# 2lampen.net
KiCad netlist of a schematic drawn in EAGLE
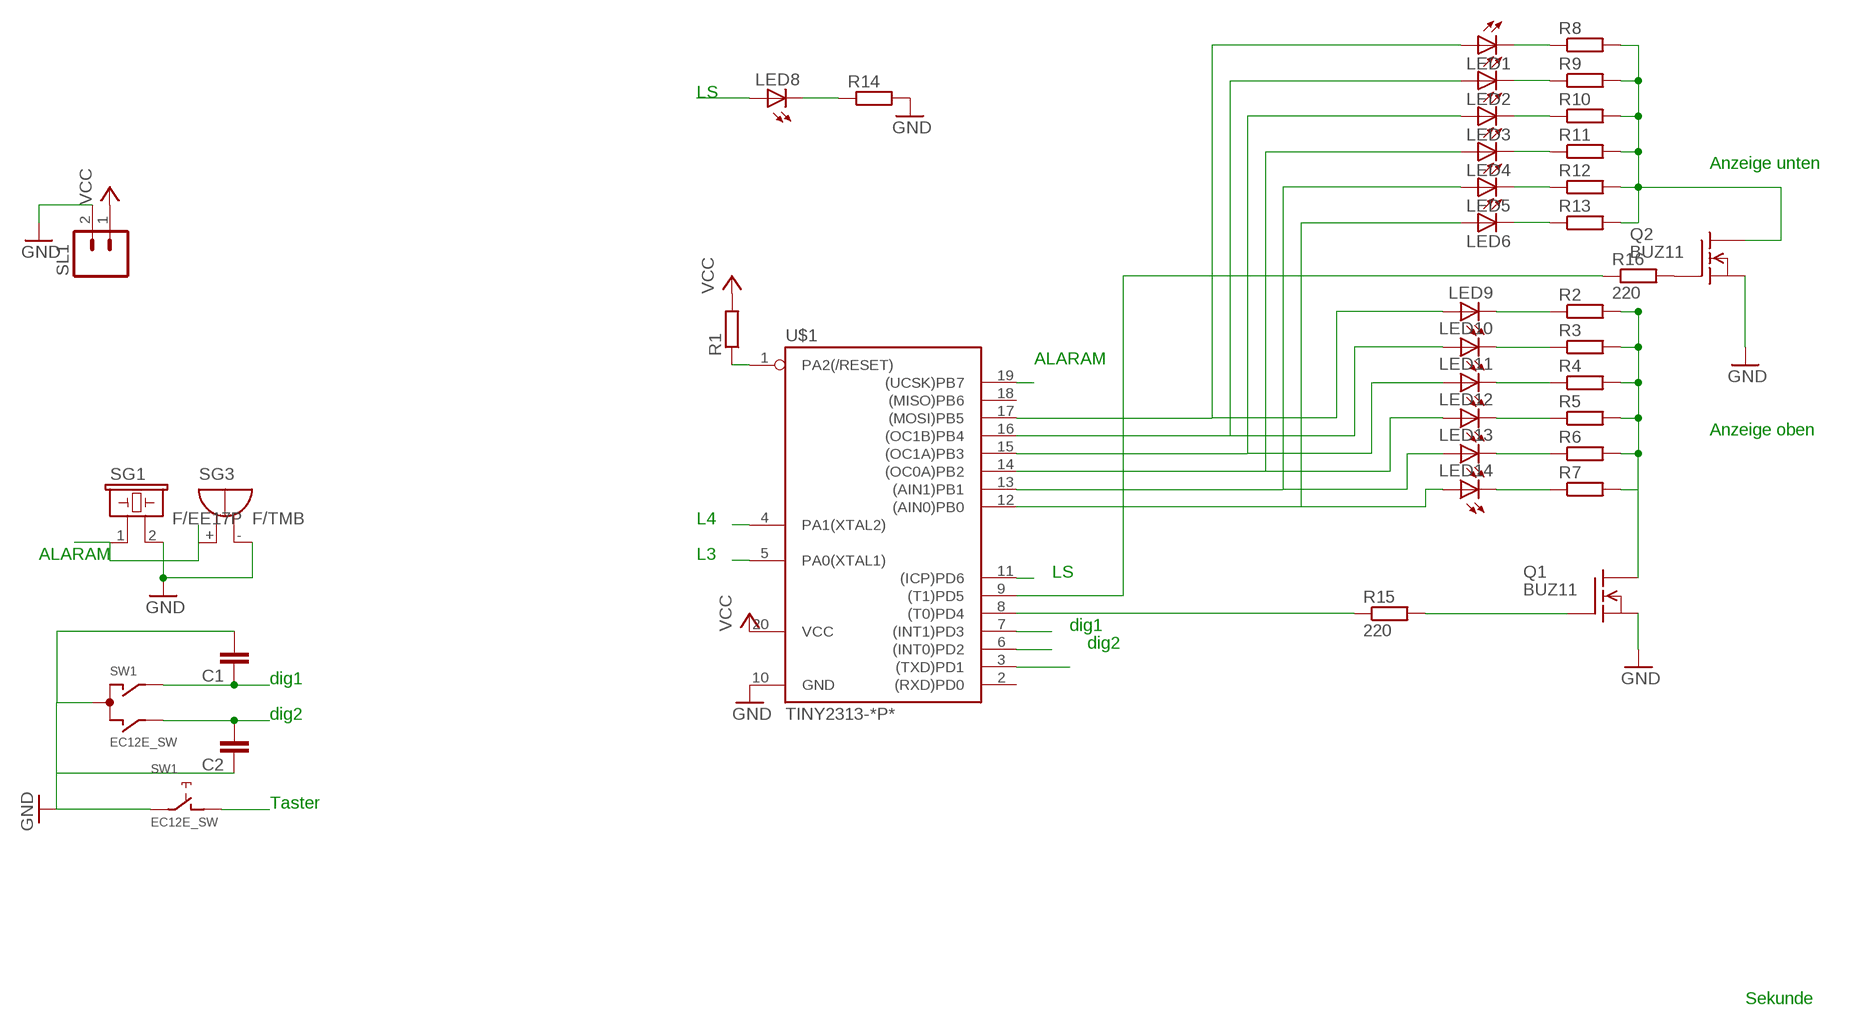
[diagram p0: schematic, sheet 1]

(export (version "E")
  (design (tool "Eeschema 10.0.6"))
  (components
    (comp (ref "C1")
      (value "C-EU025-025X050")
      (footprint "eagle-import:C025-025X050")
      (libsource (lib "eagle-import") (part "C-EU025-025X050"))
    )
    (comp (ref "C2")
      (value "C-EU025-025X050")
      (footprint "eagle-import:C025-025X050")
      (libsource (lib "eagle-import") (part "C-EU025-025X050"))
    )
    (comp (ref "LED1")
      (value "LED5MM")
      (footprint "eagle-import:LED5MM")
      (libsource (lib "eagle-import") (part "LED5MM"))
    )
    (comp (ref "LED2")
      (value "LED5MM")
      (footprint "eagle-import:LED5MM")
      (libsource (lib "eagle-import") (part "LED5MM"))
    )
    (comp (ref "LED3")
      (value "LED5MM")
      (footprint "eagle-import:LED5MM")
      (libsource (lib "eagle-import") (part "LED5MM"))
    )
    (comp (ref "LED4")
      (value "LED5MM")
      (footprint "eagle-import:LED5MM")
      (libsource (lib "eagle-import") (part "LED5MM"))
    )
    (comp (ref "LED5")
      (value "LED5MM")
      (footprint "eagle-import:LED5MM")
      (libsource (lib "eagle-import") (part "LED5MM"))
    )
    (comp (ref "LED6")
      (value "LED5MM")
      (footprint "eagle-import:LED5MM")
      (libsource (lib "eagle-import") (part "LED5MM"))
    )
    (comp (ref "LED8")
      (value "LED3MM")
      (footprint "eagle-import:LED3MM")
      (libsource (lib "eagle-import") (part "LED3MM"))
    )
    (comp (ref "LED9")
      (value "LED5MM")
      (footprint "eagle-import:LED5MM")
      (libsource (lib "eagle-import") (part "LED5MM"))
    )
    (comp (ref "LED10")
      (value "LED5MM")
      (footprint "eagle-import:LED5MM")
      (libsource (lib "eagle-import") (part "LED5MM"))
    )
    (comp (ref "LED11")
      (value "LED5MM")
      (footprint "eagle-import:LED5MM")
      (libsource (lib "eagle-import") (part "LED5MM"))
    )
    (comp (ref "LED12")
      (value "LED5MM")
      (footprint "eagle-import:LED5MM")
      (libsource (lib "eagle-import") (part "LED5MM"))
    )
    (comp (ref "LED13")
      (value "LED5MM")
      (footprint "eagle-import:LED5MM")
      (libsource (lib "eagle-import") (part "LED5MM"))
    )
    (comp (ref "LED14")
      (value "LED5MM")
      (footprint "eagle-import:LED5MM")
      (libsource (lib "eagle-import") (part "LED5MM"))
    )
    (comp (ref "Q1")
      (value "BUZ11")
      (footprint "eagle-import:TO220")
      (libsource (lib "eagle-import") (part "BUZ11"))
    )
    (comp (ref "Q2")
      (value "BUZ11")
      (footprint "eagle-import:TO220")
      (libsource (lib "eagle-import") (part "BUZ11"))
    )
    (comp (ref "R1")
      (value "R-EU_0204/7")
      (footprint "eagle-import:0204_7")
      (libsource (lib "eagle-import") (part "R-EU_0204/7"))
    )
    (comp (ref "R2")
      (value "R-EU_0204/2V")
      (footprint "eagle-import:0204V")
      (libsource (lib "eagle-import") (part "R-EU_0204/2V"))
    )
    (comp (ref "R3")
      (value "R-EU_0204/2V")
      (footprint "eagle-import:0204V")
      (libsource (lib "eagle-import") (part "R-EU_0204/2V"))
    )
    (comp (ref "R4")
      (value "R-EU_0204/2V")
      (footprint "eagle-import:0204V")
      (libsource (lib "eagle-import") (part "R-EU_0204/2V"))
    )
    (comp (ref "R5")
      (value "R-EU_0204/2V")
      (footprint "eagle-import:0204V")
      (libsource (lib "eagle-import") (part "R-EU_0204/2V"))
    )
    (comp (ref "R6")
      (value "R-EU_0204/2V")
      (footprint "eagle-import:0204V")
      (libsource (lib "eagle-import") (part "R-EU_0204/2V"))
    )
    (comp (ref "R7")
      (value "R-EU_0204/2V")
      (footprint "eagle-import:0204V")
      (libsource (lib "eagle-import") (part "R-EU_0204/2V"))
    )
    (comp (ref "R8")
      (value "R-EU_0204/2V")
      (footprint "eagle-import:0204V")
      (libsource (lib "eagle-import") (part "R-EU_0204/2V"))
    )
    (comp (ref "R9")
      (value "R-EU_0204/2V")
      (footprint "eagle-import:0204V")
      (libsource (lib "eagle-import") (part "R-EU_0204/2V"))
    )
    (comp (ref "R10")
      (value "R-EU_0204/2V")
      (footprint "eagle-import:0204V")
      (libsource (lib "eagle-import") (part "R-EU_0204/2V"))
    )
    (comp (ref "R11")
      (value "R-EU_0204/2V")
      (footprint "eagle-import:0204V")
      (libsource (lib "eagle-import") (part "R-EU_0204/2V"))
    )
    (comp (ref "R12")
      (value "R-EU_0204/2V")
      (footprint "eagle-import:0204V")
      (libsource (lib "eagle-import") (part "R-EU_0204/2V"))
    )
    (comp (ref "R13")
      (value "R-EU_0204/7")
      (footprint "eagle-import:0204_7")
      (libsource (lib "eagle-import") (part "R-EU_0204/7"))
    )
    (comp (ref "R14")
      (value "R-EU_0204/2V")
      (footprint "eagle-import:0204V")
      (libsource (lib "eagle-import") (part "R-EU_0204/2V"))
    )
    (comp (ref "R15")
      (value "220")
      (footprint "eagle-import:0204V")
      (libsource (lib "eagle-import") (part "R-EU_0204/2V"))
    )
    (comp (ref "R16")
      (value "220")
      (footprint "eagle-import:0204V")
      (libsource (lib "eagle-import") (part "R-EU_0204/2V"))
    )
    (comp (ref "SG1")
      (value "F/EE17P")
      (footprint "eagle-import:F_EE17P")
      (libsource (lib "eagle-import") (part "F/EE17P"))
    )
    (comp (ref "SG3")
      (value "F/TMB")
      (footprint "eagle-import:F_TMB")
      (libsource (lib "eagle-import") (part "F/TMB"))
    )
    (comp (ref "SL1")
      (value "M02")
      (footprint "eagle-import:02P")
      (libsource (lib "eagle-import") (part "M02"))
    )
    (comp (ref "SW1")
      (value "EC12E_SW")
      (footprint "eagle-import:ALPS_EC12E_SW")
      (fields (field (name "MPN") "EC12E2424407"))
      (libsource (lib "eagle-import") (part "EC12E_SW"))
    )
    (comp (ref "U$1")
      (value "TINY2313-*P*")
      (footprint "eagle-import:DIL20")
      (libsource (lib "eagle-import") (part "TINY2313-P"))
    )
  )
  (nets
    (net (code "1") (name "/ALARM") (class "Default")
      (node (ref "SG1") (pin "1") (pinfunction "1_1") (pintype "passive"))
      (node (ref "SG3") (pin "+") (pinfunction "+_+") (pintype "passive"))
      (node (ref "U$1") (pin "19") (pinfunction "(UCSK)PB7_19") (pintype "bidirectional"))
    )
    (net (code "2") (name "/DIG1") (class "Default")
      (node (ref "C1") (pin "1") (pinfunction "1_1") (pintype "passive"))
      (node (ref "SW1") (pin "A") (pinfunction "A_A") (pintype "passive"))
      (node (ref "U$1") (pin "7") (pinfunction "(INT1)PD3_7") (pintype "bidirectional"))
    )
    (net (code "3") (name "/DIG2") (class "Default")
      (node (ref "C2") (pin "2") (pinfunction "2_2") (pintype "passive"))
      (node (ref "SW1") (pin "B") (pinfunction "B_B") (pintype "passive"))
      (node (ref "U$1") (pin "6") (pinfunction "(INT0)PD2_6") (pintype "bidirectional"))
    )
    (net (code "4") (name "/L3") (class "Default")
      (node (ref "LED11") (pin "A") (pinfunction "A_A") (pintype "passive"))
      (node (ref "LED3") (pin "A") (pinfunction "A_A") (pintype "passive"))
      (node (ref "U$1") (pin "15") (pinfunction "(OC1A)PB3_15") (pintype "bidirectional"))
      (node (ref "U$1") (pin "5") (pinfunction "PA0(XTAL1)_5") (pintype "bidirectional"))
    )
    (net (code "5") (name "/L4") (class "Default")
      (node (ref "LED12") (pin "A") (pinfunction "A_A") (pintype "passive"))
      (node (ref "LED4") (pin "A") (pinfunction "A_A") (pintype "passive"))
      (node (ref "U$1") (pin "14") (pinfunction "(OC0A)PB2_14") (pintype "bidirectional"))
      (node (ref "U$1") (pin "4") (pinfunction "PA1(XTAL2)_4") (pintype "bidirectional"))
    )
    (net (code "6") (name "/LS") (class "Default")
      (node (ref "LED8") (pin "A") (pinfunction "A_A") (pintype "passive"))
      (node (ref "U$1") (pin "11") (pinfunction "(ICP)PD6_11") (pintype "bidirectional"))
    )
    (net (code "7") (name "GND") (class "Default")
      (node (ref "C1") (pin "2") (pinfunction "2_2") (pintype "passive"))
      (node (ref "C2") (pin "1") (pinfunction "1_1") (pintype "passive"))
      (node (ref "Q1") (pin "3") (pinfunction "S_3") (pintype "passive"))
      (node (ref "Q2") (pin "3") (pinfunction "S_3") (pintype "passive"))
      (node (ref "R14") (pin "2") (pinfunction "2_2") (pintype "passive"))
      (node (ref "SG1") (pin "2") (pinfunction "2_2") (pintype "passive"))
      (node (ref "SG3") (pin "-") (pinfunction "-_-") (pintype "passive"))
      (node (ref "SL1") (pin "2") (pinfunction "2_2") (pintype "passive"))
      (node (ref "SW1") (pin "C") (pinfunction "C_C") (pintype "passive"))
      (node (ref "SW1") (pin "E") (pinfunction "2_E") (pintype "passive"))
      (node (ref "U$1") (pin "10") (pinfunction "GND_10") (pintype "power_in"))
    )
    (net (code "8") (name "Net-(LED1-C)") (class "Default")
      (node (ref "LED1") (pin "K") (pinfunction "C_K") (pintype "passive"))
      (node (ref "R8") (pin "1") (pinfunction "1_1") (pintype "passive"))
    )
    (net (code "9") (name "Net-(LED2-C)") (class "Default")
      (node (ref "LED2") (pin "K") (pinfunction "C_K") (pintype "passive"))
      (node (ref "R9") (pin "1") (pinfunction "1_1") (pintype "passive"))
    )
    (net (code "10") (name "Net-(LED3-C)") (class "Default")
      (node (ref "LED3") (pin "K") (pinfunction "C_K") (pintype "passive"))
      (node (ref "R10") (pin "1") (pinfunction "1_1") (pintype "passive"))
    )
    (net (code "11") (name "Net-(LED4-C)") (class "Default")
      (node (ref "LED4") (pin "K") (pinfunction "C_K") (pintype "passive"))
      (node (ref "R11") (pin "1") (pinfunction "1_1") (pintype "passive"))
    )
    (net (code "12") (name "Net-(LED5-C)") (class "Default")
      (node (ref "LED5") (pin "K") (pinfunction "C_K") (pintype "passive"))
      (node (ref "R12") (pin "1") (pinfunction "1_1") (pintype "passive"))
    )
    (net (code "13") (name "Net-(LED6-C)") (class "Default")
      (node (ref "LED6") (pin "K") (pinfunction "C_K") (pintype "passive"))
      (node (ref "R13") (pin "1") (pinfunction "1_1") (pintype "passive"))
    )
    (net (code "14") (name "Net-(LED8-C)") (class "Default")
      (node (ref "LED8") (pin "K") (pinfunction "C_K") (pintype "passive"))
      (node (ref "R14") (pin "1") (pinfunction "1_1") (pintype "passive"))
    )
    (net (code "15") (name "Net-(LED9-C)") (class "Default")
      (node (ref "LED9") (pin "K") (pinfunction "C_K") (pintype "passive"))
      (node (ref "R2") (pin "1") (pinfunction "1_1") (pintype "passive"))
    )
    (net (code "16") (name "Net-(LED10-C)") (class "Default")
      (node (ref "LED10") (pin "K") (pinfunction "C_K") (pintype "passive"))
      (node (ref "R3") (pin "1") (pinfunction "1_1") (pintype "passive"))
    )
    (net (code "17") (name "Net-(LED11-C)") (class "Default")
      (node (ref "LED11") (pin "K") (pinfunction "C_K") (pintype "passive"))
      (node (ref "R4") (pin "1") (pinfunction "1_1") (pintype "passive"))
    )
    (net (code "18") (name "Net-(LED12-C)") (class "Default")
      (node (ref "LED12") (pin "K") (pinfunction "C_K") (pintype "passive"))
      (node (ref "R5") (pin "1") (pinfunction "1_1") (pintype "passive"))
    )
    (net (code "19") (name "Net-(LED13-C)") (class "Default")
      (node (ref "LED13") (pin "K") (pinfunction "C_K") (pintype "passive"))
      (node (ref "R6") (pin "1") (pinfunction "1_1") (pintype "passive"))
    )
    (net (code "20") (name "Net-(LED14-C)") (class "Default")
      (node (ref "LED14") (pin "K") (pinfunction "C_K") (pintype "passive"))
      (node (ref "R7") (pin "1") (pinfunction "1_1") (pintype "passive"))
    )
    (net (code "21") (name "Net-(Q1-D)") (class "Default")
      (node (ref "Q1") (pin "2") (pinfunction "D_2") (pintype "passive"))
      (node (ref "R2") (pin "2") (pinfunction "2_2") (pintype "passive"))
      (node (ref "R3") (pin "2") (pinfunction "2_2") (pintype "passive"))
      (node (ref "R4") (pin "2") (pinfunction "2_2") (pintype "passive"))
      (node (ref "R5") (pin "2") (pinfunction "2_2") (pintype "passive"))
      (node (ref "R6") (pin "2") (pinfunction "2_2") (pintype "passive"))
      (node (ref "R7") (pin "2") (pinfunction "2_2") (pintype "passive"))
    )
    (net (code "22") (name "Net-(Q1-G)") (class "Default")
      (node (ref "Q1") (pin "1") (pinfunction "G_1") (pintype "passive"))
      (node (ref "R15") (pin "2") (pinfunction "2_2") (pintype "passive"))
    )
    (net (code "23") (name "Net-(Q2-D)") (class "Default")
      (node (ref "Q2") (pin "2") (pinfunction "D_2") (pintype "passive"))
      (node (ref "R10") (pin "2") (pinfunction "2_2") (pintype "passive"))
      (node (ref "R11") (pin "2") (pinfunction "2_2") (pintype "passive"))
      (node (ref "R12") (pin "2") (pinfunction "2_2") (pintype "passive"))
      (node (ref "R13") (pin "2") (pinfunction "2_2") (pintype "passive"))
      (node (ref "R8") (pin "2") (pinfunction "2_2") (pintype "passive"))
      (node (ref "R9") (pin "2") (pinfunction "2_2") (pintype "passive"))
    )
    (net (code "24") (name "Net-(Q2-G)") (class "Default")
      (node (ref "Q2") (pin "1") (pinfunction "G_1") (pintype "passive"))
      (node (ref "R16") (pin "2") (pinfunction "2_2") (pintype "passive"))
    )
    (net (code "25") (name "Net-(U$1-(AIN0)PB0)") (class "Default")
      (node (ref "LED14") (pin "A") (pinfunction "A_A") (pintype "passive"))
      (node (ref "LED6") (pin "A") (pinfunction "A_A") (pintype "passive"))
      (node (ref "U$1") (pin "12") (pinfunction "(AIN0)PB0_12") (pintype "bidirectional"))
    )
    (net (code "26") (name "Net-(U$1-(AIN1)PB1)") (class "Default")
      (node (ref "LED13") (pin "A") (pinfunction "A_A") (pintype "passive"))
      (node (ref "LED5") (pin "A") (pinfunction "A_A") (pintype "passive"))
      (node (ref "U$1") (pin "13") (pinfunction "(AIN1)PB1_13") (pintype "bidirectional"))
    )
    (net (code "27") (name "Net-(U$1-(MOSI)PB5)") (class "Default")
      (node (ref "LED1") (pin "A") (pinfunction "A_A") (pintype "passive"))
      (node (ref "LED9") (pin "A") (pinfunction "A_A") (pintype "passive"))
      (node (ref "U$1") (pin "17") (pinfunction "(MOSI)PB5_17") (pintype "bidirectional"))
    )
    (net (code "28") (name "Net-(U$1-(OC1B)PB4)") (class "Default")
      (node (ref "LED10") (pin "A") (pinfunction "A_A") (pintype "passive"))
      (node (ref "LED2") (pin "A") (pinfunction "A_A") (pintype "passive"))
      (node (ref "U$1") (pin "16") (pinfunction "(OC1B)PB4_16") (pintype "bidirectional"))
    )
    (net (code "29") (name "Net-(U$1-(T0)PD4)") (class "Default")
      (node (ref "R15") (pin "1") (pinfunction "1_1") (pintype "passive"))
      (node (ref "U$1") (pin "8") (pinfunction "(T0)PD4_8") (pintype "bidirectional"))
    )
    (net (code "30") (name "Net-(U$1-(T1)PD5)") (class "Default")
      (node (ref "R16") (pin "1") (pinfunction "1_1") (pintype "passive"))
      (node (ref "U$1") (pin "9") (pinfunction "(T1)PD5_9") (pintype "bidirectional"))
    )
    (net (code "31") (name "Net-(U$1-PA2({slash}RESET))") (class "Default")
      (node (ref "R1") (pin "1") (pinfunction "1_1") (pintype "passive"))
      (node (ref "U$1") (pin "1") (pinfunction "PA2(/RESET)_1") (pintype "input"))
    )
    (net (code "32") (name "VCC") (class "Default")
      (node (ref "R1") (pin "2") (pinfunction "2_2") (pintype "passive"))
      (node (ref "SL1") (pin "1") (pinfunction "1_1") (pintype "passive"))
      (node (ref "U$1") (pin "20") (pinfunction "VCC_20") (pintype "power_in"))
    )
    (net (code "33") (name "unconnected-(SW1B-1-PadD)") (class "Default")
      (node (ref "SW1") (pin "D") (pinfunction "1_D") (pintype "passive"))
    )
    (net (code "34") (name "unconnected-(U$1-(MISO)PB6-Pad18)") (class "Default")
      (node (ref "U$1") (pin "18") (pinfunction "(MISO)PB6_18") (pintype "bidirectional"))
    )
    (net (code "35") (name "unconnected-(U$1-(RXD)PD0-Pad2)") (class "Default")
      (node (ref "U$1") (pin "2") (pinfunction "(RXD)PD0_2") (pintype "bidirectional"))
    )
    (net (code "36") (name "unconnected-(U$1-(TXD)PD1-Pad3)") (class "Default")
      (node (ref "U$1") (pin "3") (pinfunction "(TXD)PD1_3") (pintype "bidirectional"))
    )
  )
)
